# mcu_blk.net
KiCad netlist of a schematic drawn in Altium Designer
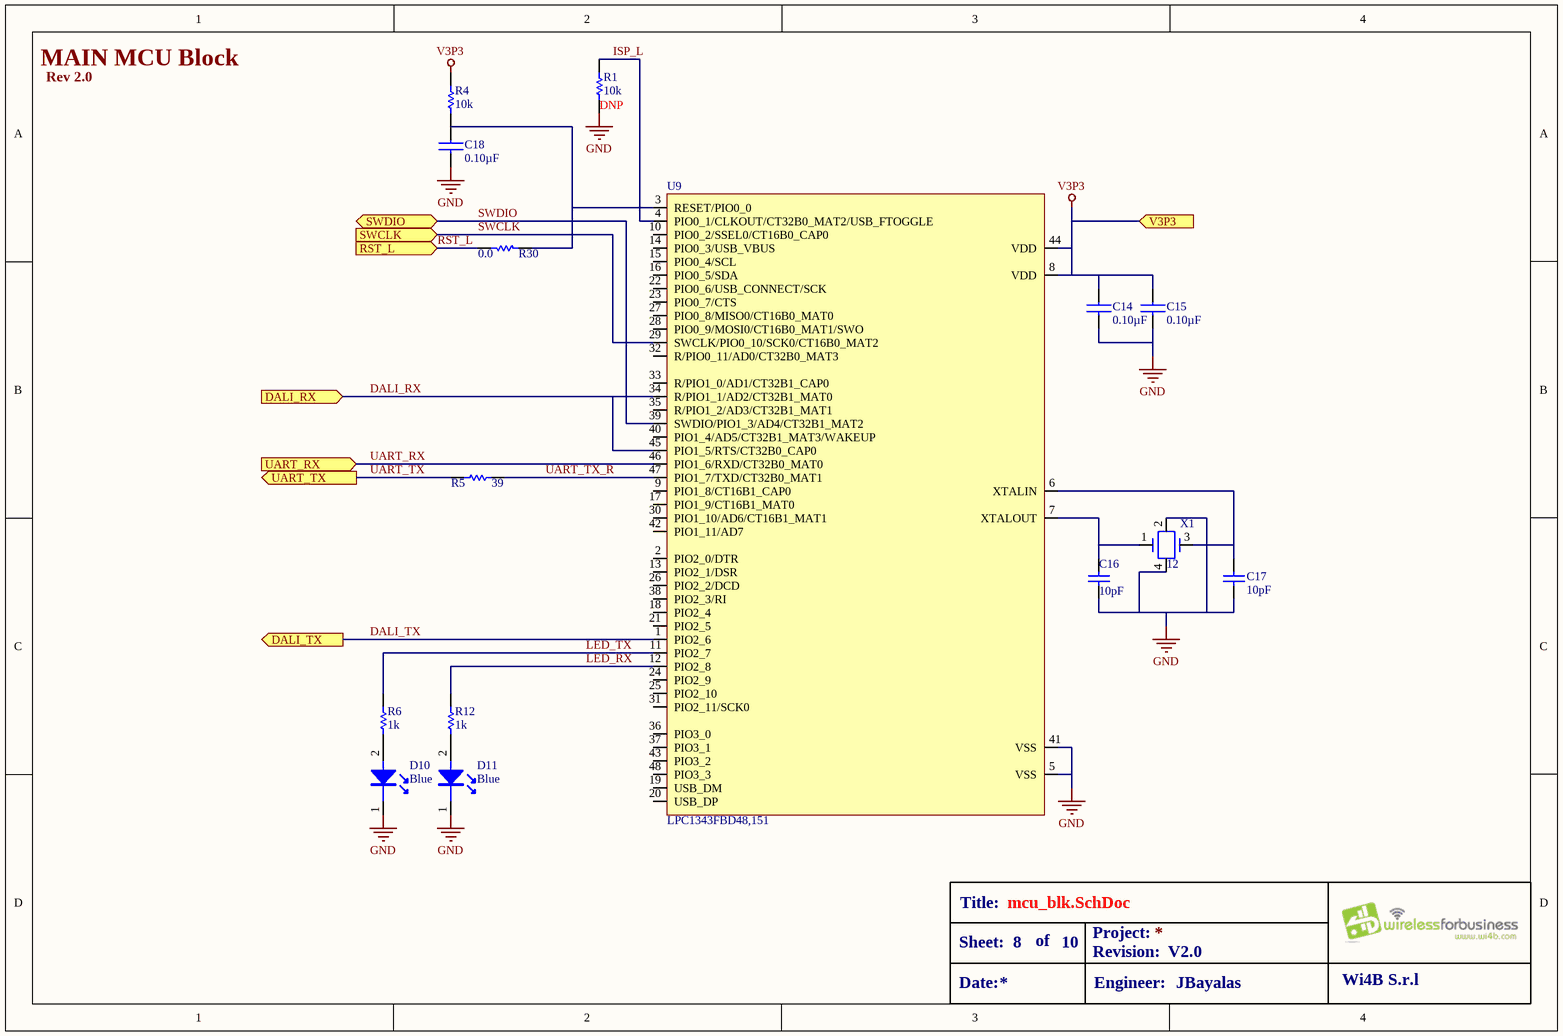
[diagram p0: mcu_blk.SchDoc]

(export (version "E")
  (design (tool "Eeschema 10.0.6"))
  (components
    (comp (ref "C14")
      (value "0.10µF")
      (footprint "C0402")
      (description "CAP CER 0.1UF 50V X7R 0402")
      (fields (field (name "MPN") "GRM155R71H104ME14D"))
      (libsource (lib "Capacitor") (part "GRM155R71H104ME14D"))
    )
    (comp (ref "C15")
      (value "0.10µF")
      (footprint "C0402")
      (description "CAP CER 0.1UF 50V X7R 0402")
      (fields (field (name "MPN") "GRM155R71H104ME14D"))
      (libsource (lib "Capacitor") (part "GRM155R71H104ME14D"))
    )
    (comp (ref "C16")
      (value "10pF")
      (footprint "C0402")
      (description "CAP CER 10PF 50V 1% NP0 0402")
      (fields (field (name "MPN") "GRM1555C1H100FA01D"))
      (libsource (lib "Capacitor") (part "GRM1555C1H100FA01D"))
    )
    (comp (ref "C17")
      (value "10pF")
      (footprint "C0402")
      (description "CAP CER 10PF 50V 1% NP0 0402")
      (fields (field (name "MPN") "GRM1555C1H100FA01D"))
      (libsource (lib "Capacitor") (part "GRM1555C1H100FA01D"))
    )
    (comp (ref "C18")
      (value "0.10µF")
      (footprint "C0402")
      (description "CAP CER 0.1UF 50V X7R 0402")
      (fields (field (name "MPN") "GRM155R71H104ME14D"))
      (libsource (lib "Capacitor") (part "GRM155R71H104ME14D"))
    )
    (comp (ref "D10")
      (value "Blue")
      (footprint "LED0402(BLUE)")
      (description "LED BLUE 0402 SMD")
      (fields (field (name "MPN") "VLMB1500-GS08"))
      (libsource (lib "Diode") (part "VLMB1500-GS08"))
    )
    (comp (ref "D11")
      (value "Blue")
      (footprint "LED0402(BLUE)")
      (description "LED BLUE 0402 SMD")
      (fields (field (name "MPN") "VLMB1500-GS08"))
      (libsource (lib "Diode") (part "VLMB1500-GS08"))
    )
    (comp (ref "R1")
      (value "10k")
      (footprint "R0402")
      (description "RES SMD 10K OHM 1% 1/10W 0402")
      (fields (field (name "MPN") "MCS04020C1002FE000") (field (name "DNP") "DNP"))
      (libsource (lib "Res") (part "MCS04020C1002FE000"))
    )
    (comp (ref "R4")
      (value "10k")
      (footprint "R0402")
      (description "RES SMD 10K OHM 1% 1/10W 0402")
      (fields (field (name "MPN") "ERJ-2RKF1002X"))
      (libsource (lib "Res") (part "ERJ-2RKF1002X"))
    )
    (comp (ref "R5")
      (value "39")
      (footprint "R0402")
      (description "RES SMD 39 OHM 1% 1/16W 0402")
      (fields (field (name "MPN") "CRCW040239R0FKED"))
      (libsource (lib "Res") (part "CRCW040239R0FKED"))
    )
    (comp (ref "R6")
      (value "1k")
      (footprint "R0402")
      (description "RES SMD 1K OHM 1% 1/10W 0402")
      (fields (field (name "MPN") "ERJ-2RKF1001X"))
      (libsource (lib "Res") (part "ERJ-2RKF1001X"))
    )
    (comp (ref "R12")
      (value "1k")
      (footprint "R0402")
      (description "RES SMD 1K OHM 1% 1/10W 0402")
      (fields (field (name "MPN") "ERJ-2RKF1001X"))
      (libsource (lib "Res") (part "ERJ-2RKF1001X"))
    )
    (comp (ref "R30")
      (value "0.0")
      (footprint "R0402")
      (description "RES SMD 0.0OHM JUMPER 1/16W 0402")
      (fields (field (name "MPN") "CRCW04020000Z0ED"))
      (libsource (lib "Res") (part "CRCW04020000Z0ED"))
    )
    (comp (ref "U9")
      (value "~")
      (footprint "LQFP-48(7x7mm body)")
      (description "IC MCU ARM 32KB FLASH 48LQFP")
      (fields (field (name "MPN") "LPC1343FBD48,151"))
      (libsource (lib "IC") (part "LPC1343FBD48,151"))
    )
    (comp (ref "X1")
      (value "ABM8G-12.000MHZ-18-D2Y-T")
      (footprint "4SMD-crystal")
      (description "ABRACON - ABM8G-12.000MHZ-18-D2Y-T - CRYSTAL, 12MHz,18pF, 3.2mm x 2.5mm SMD, FULL REEL")
      (fields (field (name "MANUFACTURER") "ABRACON") (field (name "FREQUENCY NOM") "12"))
      (libsource (lib "Crystal") (part "ABM8G-12.000MHZ-18-D2Y-T"))
    )
  )
  (nets
    (net (code "1") (name "/DALI_RX") (class "Default")
      (node (ref "U9") (pin "34") (pinfunction "R/PIO1_1/AD2/CT32B1_MAT0_34") (pintype "passive"))
      (node (ref "U9") (pin "45") (pinfunction "PIO1_5/RTS/CT32B0_CAP0_45") (pintype "passive"))
    )
    (net (code "2") (name "/DALI_TX") (class "Default")
      (node (ref "U9") (pin "1") (pinfunction "PIO2_6_1") (pintype "passive"))
    )
    (net (code "3") (name "/ISP_L") (class "Default")
      (node (ref "R1") (pin "2") (pinfunction "2_2") (pintype "passive"))
      (node (ref "U9") (pin "4") (pinfunction "PIO0_1/CLKOUT/CT32B0_MAT2/USB_FTOGGLE_4") (pintype "passive"))
    )
    (net (code "4") (name "/LED_RX") (class "Default")
      (node (ref "R12") (pin "2") (pinfunction "2_2") (pintype "passive"))
      (node (ref "U9") (pin "12") (pinfunction "PIO2_8_12") (pintype "passive"))
    )
    (net (code "5") (name "/LED_TX") (class "Default")
      (node (ref "R6") (pin "2") (pinfunction "2_2") (pintype "passive"))
      (node (ref "U9") (pin "11") (pinfunction "PIO2_7_11") (pintype "passive"))
    )
    (net (code "6") (name "/RST_L") (class "Default")
      (node (ref "R30") (pin "1") (pinfunction "1_1") (pintype "passive"))
    )
    (net (code "7") (name "/SWCLK") (class "Default")
      (node (ref "U9") (pin "29") (pinfunction "SWCLK/PIO0_10/SCK0/CT16B0_MAT2_29") (pintype "passive"))
    )
    (net (code "8") (name "/SWDIO") (class "Default")
      (node (ref "U9") (pin "39") (pinfunction "SWDIO/PIO1_3/AD4/CT32B1_MAT2_39") (pintype "passive"))
    )
    (net (code "9") (name "/UART_RX") (class "Default")
      (node (ref "U9") (pin "46") (pinfunction "PIO1_6/RXD/CT32B0_MAT0_46") (pintype "passive"))
    )
    (net (code "10") (name "/UART_TX") (class "Default")
      (node (ref "R5") (pin "1") (pinfunction "1_1") (pintype "passive"))
    )
    (net (code "11") (name "/UART_TX_R") (class "Default")
      (node (ref "R5") (pin "2") (pinfunction "2_2") (pintype "passive"))
      (node (ref "U9") (pin "47") (pinfunction "PIO1_7/TXD/CT32B0_MAT1_47") (pintype "passive"))
    )
    (net (code "12") (name "GND") (class "Default")
      (node (ref "C14") (pin "2") (pinfunction "2_2") (pintype "passive"))
      (node (ref "C15") (pin "2") (pinfunction "2_2") (pintype "passive"))
      (node (ref "C16") (pin "1") (pinfunction "1_1") (pintype "passive"))
      (node (ref "C17") (pin "1") (pinfunction "1_1") (pintype "passive"))
      (node (ref "C18") (pin "2") (pinfunction "2_2") (pintype "passive"))
      (node (ref "D10") (pin "1") (pinfunction "1_1") (pintype "passive"))
      (node (ref "D11") (pin "1") (pinfunction "1_1") (pintype "passive"))
      (node (ref "R1") (pin "1") (pinfunction "1_1") (pintype "passive"))
      (node (ref "U9") (pin "41") (pinfunction "VSS_41") (pintype "passive"))
      (node (ref "U9") (pin "5") (pinfunction "VSS_5") (pintype "passive"))
      (node (ref "X1") (pin "2") (pinfunction "2_2") (pintype "passive"))
      (node (ref "X1") (pin "4") (pinfunction "4_4") (pintype "passive"))
    )
    (net (code "13") (name "Net-(D10-Pad2)") (class "Default")
      (node (ref "D10") (pin "2") (pinfunction "2_2") (pintype "passive"))
      (node (ref "R6") (pin "1") (pinfunction "1_1") (pintype "passive"))
    )
    (net (code "14") (name "Net-(D11-Pad2)") (class "Default")
      (node (ref "D11") (pin "2") (pinfunction "2_2") (pintype "passive"))
      (node (ref "R12") (pin "1") (pinfunction "1_1") (pintype "passive"))
    )
    (net (code "15") (name "Net-(U9-RESET{slash}PIO0_0)") (class "Default")
      (node (ref "C18") (pin "1") (pinfunction "1_1") (pintype "passive"))
      (node (ref "R30") (pin "2") (pinfunction "2_2") (pintype "passive"))
      (node (ref "R4") (pin "1") (pinfunction "1_1") (pintype "passive"))
      (node (ref "U9") (pin "3") (pinfunction "RESET/PIO0_0_3") (pintype "passive"))
    )
    (net (code "16") (name "Net-(U9-XTALIN)") (class "Default")
      (node (ref "C17") (pin "2") (pinfunction "2_2") (pintype "passive"))
      (node (ref "U9") (pin "6") (pinfunction "XTALIN_6") (pintype "passive"))
      (node (ref "X1") (pin "3") (pinfunction "3_3") (pintype "passive"))
    )
    (net (code "17") (name "Net-(U9-XTALOUT)") (class "Default")
      (node (ref "C16") (pin "2") (pinfunction "2_2") (pintype "passive"))
      (node (ref "U9") (pin "7") (pinfunction "XTALOUT_7") (pintype "passive"))
      (node (ref "X1") (pin "1") (pinfunction "1_1") (pintype "passive"))
    )
    (net (code "18") (name "V3P3") (class "Default")
      (node (ref "C14") (pin "1") (pinfunction "1_1") (pintype "passive"))
      (node (ref "C15") (pin "1") (pinfunction "1_1") (pintype "passive"))
      (node (ref "R4") (pin "2") (pinfunction "2_2") (pintype "passive"))
      (node (ref "U9") (pin "44") (pinfunction "VDD_44") (pintype "passive"))
      (node (ref "U9") (pin "8") (pinfunction "VDD_8") (pintype "passive"))
    )
    (net (code "19") (name "unconnected-(U9-PIO0_2{slash}SSEL0{slash}CT16B0_CAP0-Pad10)") (class "Default")
      (node (ref "U9") (pin "10") (pinfunction "PIO0_2/SSEL0/CT16B0_CAP0_10") (pintype "passive"))
    )
    (net (code "20") (name "unconnected-(U9-PIO0_3{slash}USB_VBUS-Pad14)") (class "Default")
      (node (ref "U9") (pin "14") (pinfunction "PIO0_3/USB_VBUS_14") (pintype "passive"))
    )
    (net (code "21") (name "unconnected-(U9-PIO0_4{slash}SCL-Pad15)") (class "Default")
      (node (ref "U9") (pin "15") (pinfunction "PIO0_4/SCL_15") (pintype "passive"))
    )
    (net (code "22") (name "unconnected-(U9-PIO0_5{slash}SDA-Pad16)") (class "Default")
      (node (ref "U9") (pin "16") (pinfunction "PIO0_5/SDA_16") (pintype "passive"))
    )
    (net (code "23") (name "unconnected-(U9-PIO0_6{slash}USB_CONNECT{slash}SCK-Pad22)") (class "Default")
      (node (ref "U9") (pin "22") (pinfunction "PIO0_6/USB_CONNECT/SCK_22") (pintype "passive"))
    )
    (net (code "24") (name "unconnected-(U9-PIO0_7{slash}CTS-Pad23)") (class "Default")
      (node (ref "U9") (pin "23") (pinfunction "PIO0_7/CTS_23") (pintype "passive"))
    )
    (net (code "25") (name "unconnected-(U9-PIO0_8{slash}MISO0{slash}CT16B0_MAT0-Pad27)") (class "Default")
      (node (ref "U9") (pin "27") (pinfunction "PIO0_8/MISO0/CT16B0_MAT0_27") (pintype "passive"))
    )
    (net (code "26") (name "unconnected-(U9-PIO0_9{slash}MOSI0{slash}CT16B0_MAT1{slash}SWO-Pad28)") (class "Default")
      (node (ref "U9") (pin "28") (pinfunction "PIO0_9/MOSI0/CT16B0_MAT1/SWO_28") (pintype "passive"))
    )
    (net (code "27") (name "unconnected-(U9-PIO1_4{slash}AD5{slash}CT32B1_MAT3{slash}WAKEUP-Pad40)") (class "Default")
      (node (ref "U9") (pin "40") (pinfunction "PIO1_4/AD5/CT32B1_MAT3/WAKEUP_40") (pintype "passive"))
    )
    (net (code "28") (name "unconnected-(U9-PIO1_8{slash}CT16B1_CAP0-Pad9)") (class "Default")
      (node (ref "U9") (pin "9") (pinfunction "PIO1_8/CT16B1_CAP0_9") (pintype "passive"))
    )
    (net (code "29") (name "unconnected-(U9-PIO1_9{slash}CT16B1_MAT0-Pad17)") (class "Default")
      (node (ref "U9") (pin "17") (pinfunction "PIO1_9/CT16B1_MAT0_17") (pintype "passive"))
    )
    (net (code "30") (name "unconnected-(U9-PIO1_10{slash}AD6{slash}CT16B1_MAT1-Pad30)") (class "Default")
      (node (ref "U9") (pin "30") (pinfunction "PIO1_10/AD6/CT16B1_MAT1_30") (pintype "passive"))
    )
    (net (code "31") (name "unconnected-(U9-PIO1_11{slash}AD7-Pad42)") (class "Default")
      (node (ref "U9") (pin "42") (pinfunction "PIO1_11/AD7_42") (pintype "passive"))
    )
    (net (code "32") (name "unconnected-(U9-PIO2_0{slash}DTR-Pad2)") (class "Default")
      (node (ref "U9") (pin "2") (pinfunction "PIO2_0/DTR_2") (pintype "passive"))
    )
    (net (code "33") (name "unconnected-(U9-PIO2_1{slash}DSR-Pad13)") (class "Default")
      (node (ref "U9") (pin "13") (pinfunction "PIO2_1/DSR_13") (pintype "passive"))
    )
    (net (code "34") (name "unconnected-(U9-PIO2_2{slash}DCD-Pad26)") (class "Default")
      (node (ref "U9") (pin "26") (pinfunction "PIO2_2/DCD_26") (pintype "passive"))
    )
    (net (code "35") (name "unconnected-(U9-PIO2_3{slash}RI-Pad38)") (class "Default")
      (node (ref "U9") (pin "38") (pinfunction "PIO2_3/RI_38") (pintype "passive"))
    )
    (net (code "36") (name "unconnected-(U9-PIO2_4-Pad18)") (class "Default")
      (node (ref "U9") (pin "18") (pinfunction "PIO2_4_18") (pintype "passive"))
    )
    (net (code "37") (name "unconnected-(U9-PIO2_5-Pad21)") (class "Default")
      (node (ref "U9") (pin "21") (pinfunction "PIO2_5_21") (pintype "passive"))
    )
    (net (code "38") (name "unconnected-(U9-PIO2_9-Pad24)") (class "Default")
      (node (ref "U9") (pin "24") (pinfunction "PIO2_9_24") (pintype "passive"))
    )
    (net (code "39") (name "unconnected-(U9-PIO2_10-Pad25)") (class "Default")
      (node (ref "U9") (pin "25") (pinfunction "PIO2_10_25") (pintype "passive"))
    )
    (net (code "40") (name "unconnected-(U9-PIO2_11{slash}SCK0-Pad31)") (class "Default")
      (node (ref "U9") (pin "31") (pinfunction "PIO2_11/SCK0_31") (pintype "passive"))
    )
    (net (code "41") (name "unconnected-(U9-PIO3_0-Pad36)") (class "Default")
      (node (ref "U9") (pin "36") (pinfunction "PIO3_0_36") (pintype "passive"))
    )
    (net (code "42") (name "unconnected-(U9-PIO3_1-Pad37)") (class "Default")
      (node (ref "U9") (pin "37") (pinfunction "PIO3_1_37") (pintype "passive"))
    )
    (net (code "43") (name "unconnected-(U9-PIO3_2-Pad43)") (class "Default")
      (node (ref "U9") (pin "43") (pinfunction "PIO3_2_43") (pintype "passive"))
    )
    (net (code "44") (name "unconnected-(U9-PIO3_3-Pad48)") (class "Default")
      (node (ref "U9") (pin "48") (pinfunction "PIO3_3_48") (pintype "passive"))
    )
    (net (code "45") (name "unconnected-(U9-R{slash}PIO0_11{slash}AD0{slash}CT32B0_MAT3-Pad32)") (class "Default")
      (node (ref "U9") (pin "32") (pinfunction "R/PIO0_11/AD0/CT32B0_MAT3_32") (pintype "passive"))
    )
    (net (code "46") (name "unconnected-(U9-R{slash}PIO1_0{slash}AD1{slash}CT32B1_CAP0-Pad33)") (class "Default")
      (node (ref "U9") (pin "33") (pinfunction "R/PIO1_0/AD1/CT32B1_CAP0_33") (pintype "passive"))
    )
    (net (code "47") (name "unconnected-(U9-R{slash}PIO1_2{slash}AD3{slash}CT32B1_MAT1-Pad35)") (class "Default")
      (node (ref "U9") (pin "35") (pinfunction "R/PIO1_2/AD3/CT32B1_MAT1_35") (pintype "passive"))
    )
    (net (code "48") (name "unconnected-(U9-USB_DM-Pad19)") (class "Default")
      (node (ref "U9") (pin "19") (pinfunction "USB_DM_19") (pintype "passive"))
    )
    (net (code "49") (name "unconnected-(U9-USB_DP-Pad20)") (class "Default")
      (node (ref "U9") (pin "20") (pinfunction "USB_DP_20") (pintype "passive"))
    )
  )
)
